# TY-PCB.net
KiCad netlist of a schematic drawn in EasyEDA Pro
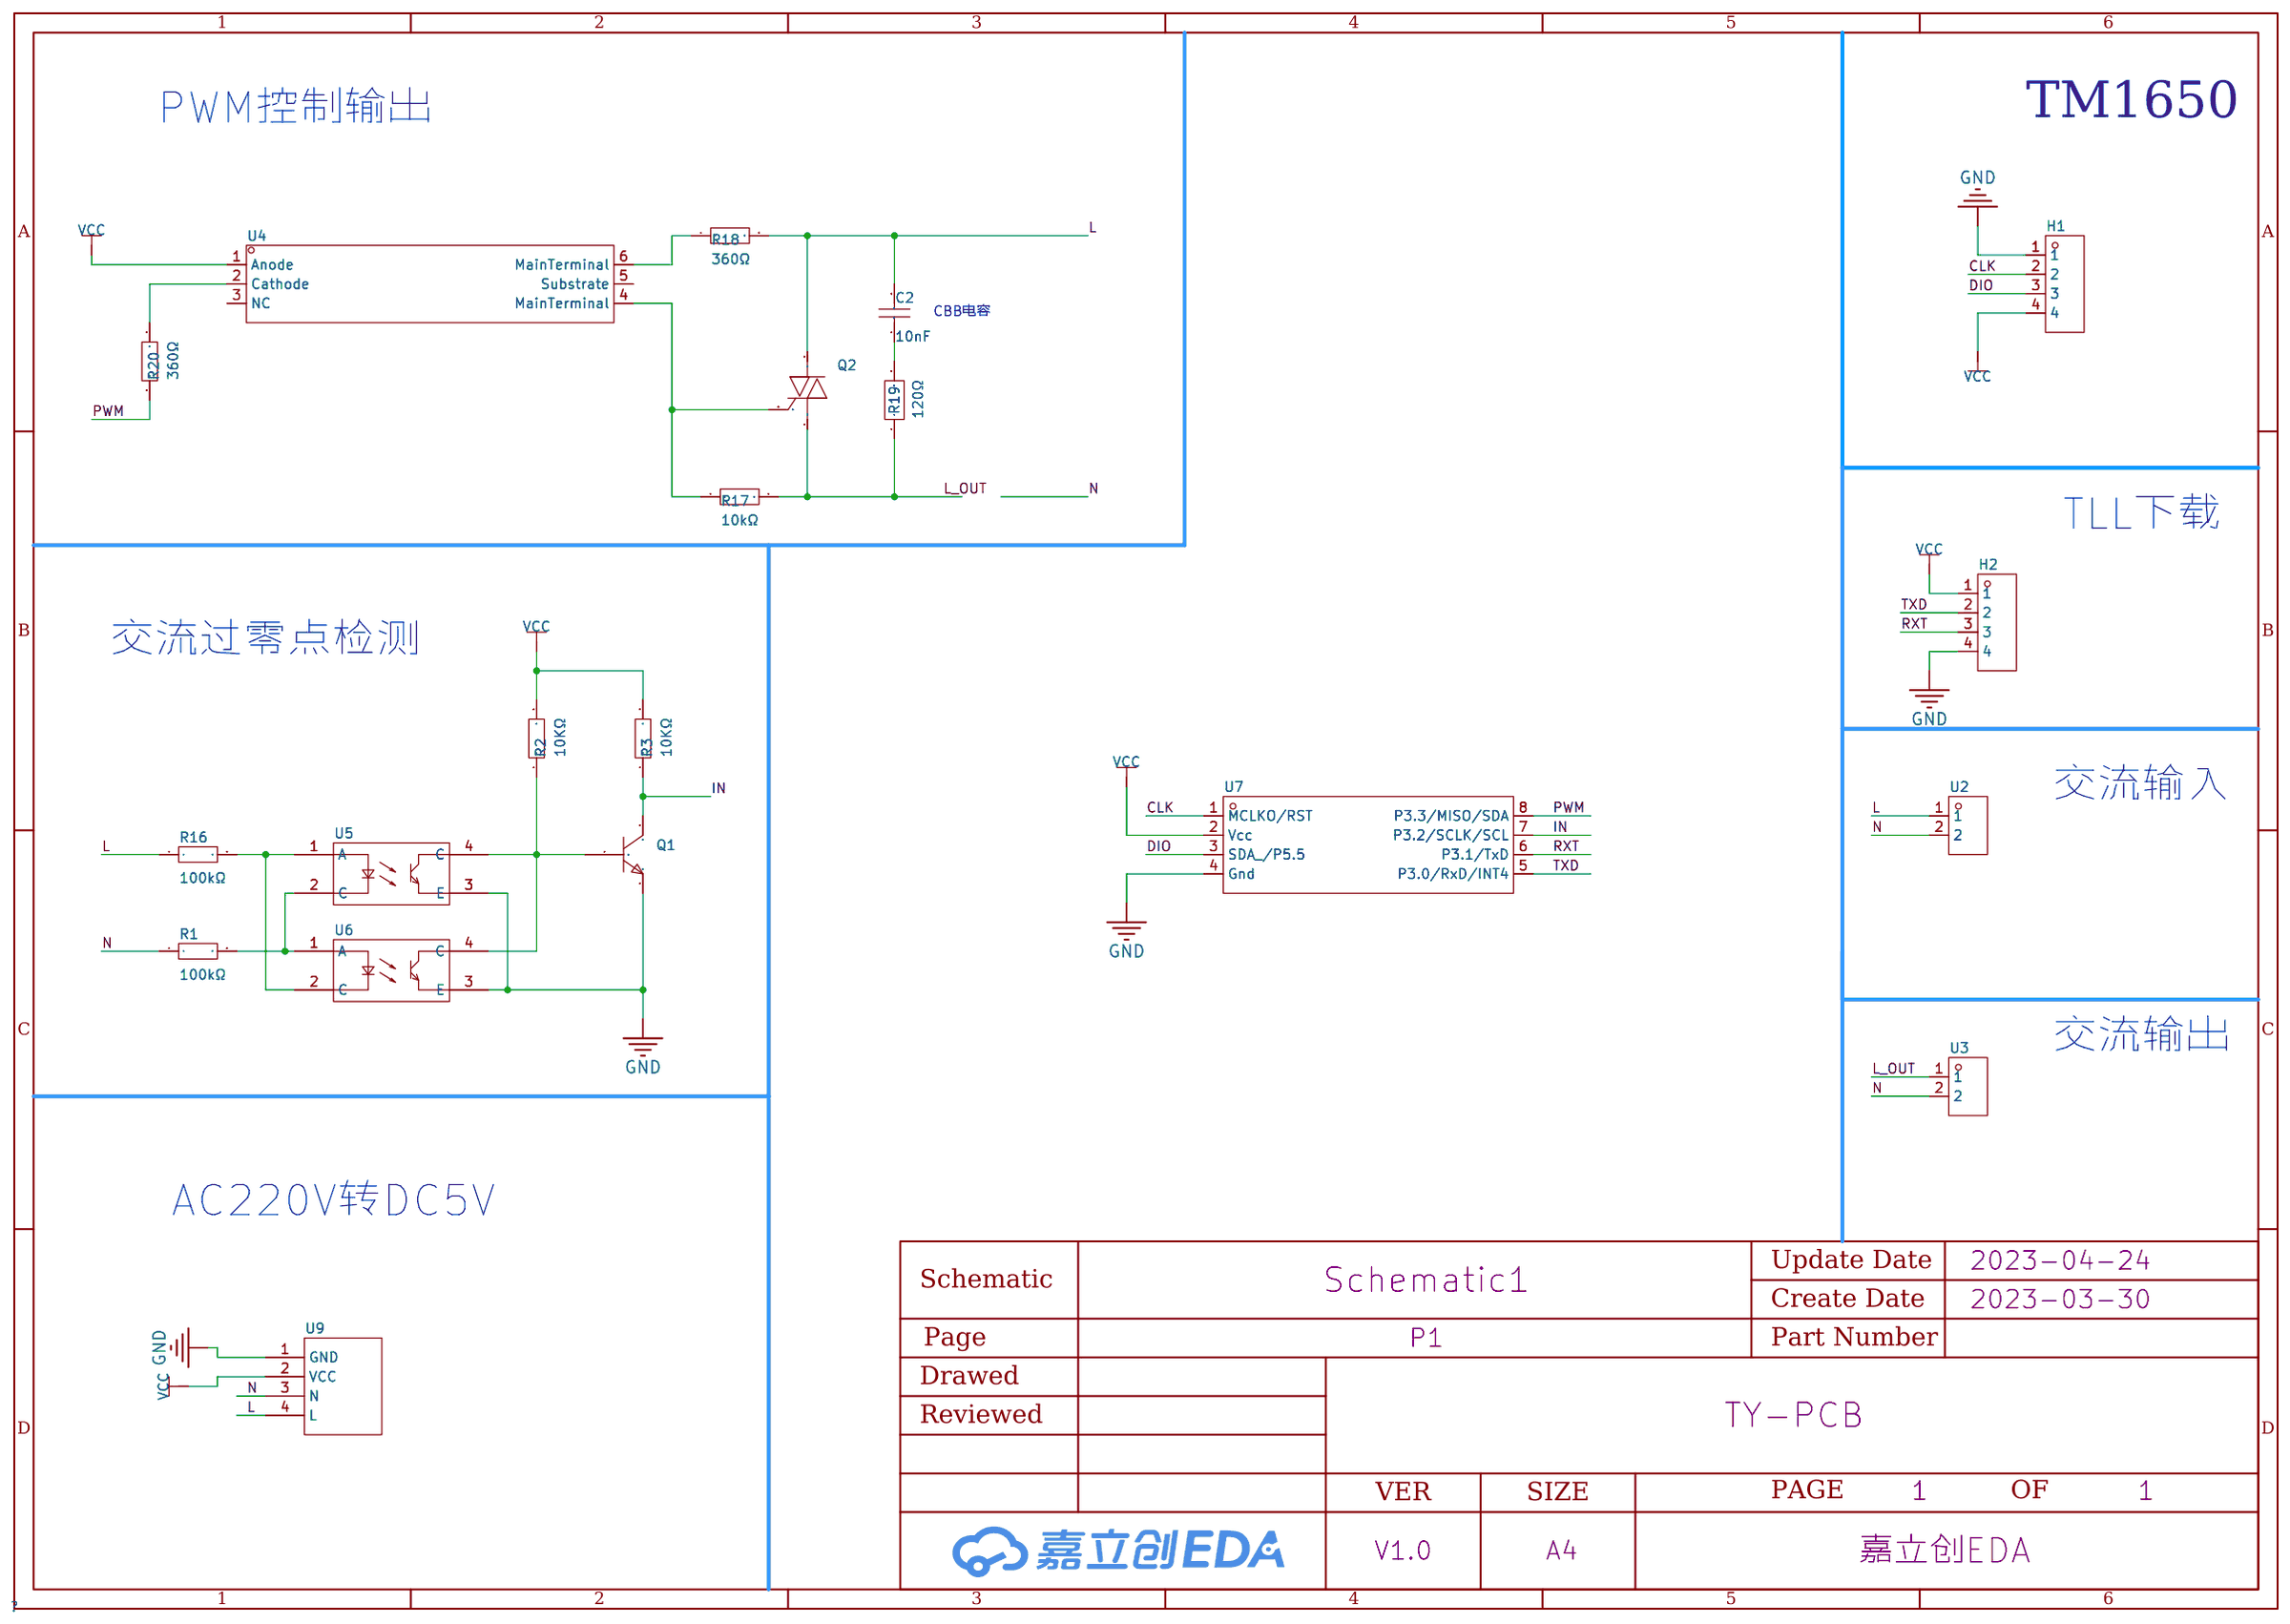
[diagram p0: schematic sheet]

(export (version "E")
  (design (tool "Eeschema 10.0.6"))
  (components
    (comp (ref "C2")
      (value "10nF")
      (footprint "easyedapro:CAP-TH_L13.0-W6.0-P10.00-D1.2")
      (description "容值:10nF;精度:±5%;额定电压:-;")
      (fields
        (field (name "Manufacturer Part") "MPP103J2J1304075LC")
        (field (name "Manufacturer") "SRD(圣融达)")
      )
      (libsource (lib "easyedapro") (part "MPP103J6130407LC"))
    )
    (comp (ref "H1")
      (value "826629-4")
      (footprint "easyedapro:HDR-TH_4P-P2.54-V-M-1")
      (fields (field (name "Manufacturer") "TE Connectivity(美国泰科)"))
      (libsource (lib "easyedapro") (part "826629-4"))
    )
    (comp (ref "H2")
      (value "826629-4")
      (footprint "easyedapro:HDR-TH_4P-P2.54-V-M-1")
      (fields (field (name "Manufacturer") "TE Connectivity(美国泰科)"))
      (libsource (lib "easyedapro") (part "826629-4"))
    )
    (comp (ref "Q1")
      (value "S8050")
      (footprint "easyedapro:TO-92-3_L4.9-W3.7-P1.27-L")
      (fields (field (name "Manufacturer") "CJ(江苏长电/长晶)"))
      (libsource (lib "easyedapro") (part "S8050_C141642"))
    )
    (comp (ref "Q2")
      (value "BTA06-800B")
      (footprint "easyedapro:TO-220-3_L10.0-W4.5-P2.54-L")
      (fields (field (name "Manufacturer") "KY(韩景元)"))
      (libsource (lib "easyedapro") (part "BTA06-800B_C2831698"))
    )
    (comp (ref "R1")
      (value "100kΩ")
      (footprint "easyedapro:R1210")
      (description "电阻类型:厚膜电阻;阻值:100kΩ;精度:±5%;功率:750mW;温度系数:±200ppm/°C;最大工作电压:200V;工作温度范围:-55°C~+125°C;")
      (fields (field (name "Manufacturer Part") "CR1210J30104G") (field (name "Manufacturer") "LIZ(丽智电子)"))
      (libsource (lib "easyedapro") (part "CR1210J30104G"))
    )
    (comp (ref "R2")
      (value "10KΩ")
      (footprint "easyedapro:R0805")
      (description "电阻类型:厚膜电阻;阻值:10kΩ;精度:±1%;功率:125mW;温度系数:±100ppm/℃;最大工作电压:150V;工作温度范围:-55℃~+155℃;")
      (fields
        (field (name "Manufacturer Part") "0805W8F1002T5E")
        (field (name "Manufacturer") "UNI-ROYAL(厚声)")
      )
      (libsource (lib "easyedapro") (part "0805W8F1002T5E"))
    )
    (comp (ref "R3")
      (value "10KΩ")
      (footprint "easyedapro:R0805")
      (description "电阻类型:厚膜电阻;阻值:10kΩ;精度:±1%;功率:125mW;温度系数:±100ppm/℃;最大工作电压:150V;工作温度范围:-55℃~+155℃;")
      (fields
        (field (name "Manufacturer Part") "0805W8F1002T5E")
        (field (name "Manufacturer") "UNI-ROYAL(厚声)")
      )
      (libsource (lib "easyedapro") (part "0805W8F1002T5E"))
    )
    (comp (ref "R16")
      (value "100kΩ")
      (footprint "easyedapro:R1210")
      (description "电阻类型:厚膜电阻;阻值:100kΩ;精度:±5%;功率:750mW;温度系数:±200ppm/°C;最大工作电压:200V;工作温度范围:-55°C~+125°C;")
      (fields (field (name "Manufacturer Part") "CR1210J30104G") (field (name "Manufacturer") "LIZ(丽智电子)"))
      (libsource (lib "easyedapro") (part "CR1210J30104G"))
    )
    (comp (ref "R17")
      (value "10kΩ")
      (footprint "easyedapro:R1210")
      (description "阻值:10kΩ;精度:±5%;功率:750mW;温度系数:±200ppm/°C;最大工作电压:200V;工作温度范围:-55°C~+155°C;")
      (fields (field (name "Manufacturer Part") "RK73B2ETTD103J") (field (name "Manufacturer") "KOA"))
      (libsource (lib "easyedapro") (part "RK73B2ETTD103J"))
    )
    (comp (ref "R18")
      (value "360Ω")
      (footprint "easyedapro:R1210")
      (description "电阻类型:厚膜电阻;阻值:360Ω;精度:±5%;功率:750mW;温度系数:±200ppm/°C;最大工作电压:200V;工作温度范围:-55°C~+125°C;")
      (fields (field (name "Manufacturer Part") "CR1210J30361G") (field (name "Manufacturer") "LIZ(丽智电子)"))
      (libsource (lib "easyedapro") (part "CR1210J30361G"))
    )
    (comp (ref "R19")
      (value "120Ω")
      (footprint "easyedapro:R2512")
      (description "阻值:120Ω;精度:±5%;功率:2W;最大工作电压:200V;工作温度范围:-55℃~+155℃;")
      (fields (field (name "Manufacturer Part") "RC2512JK-7W120RL") (field (name "Manufacturer") "YAGEO(国巨)"))
      (libsource (lib "easyedapro") (part "RC2512JK-7W120RL"))
    )
    (comp (ref "R20")
      (value "360Ω")
      (footprint "easyedapro:R0805")
      (description "电阻类型:厚膜电阻;阻值:10kΩ;精度:±1%;功率:125mW;温度系数:±100ppm/℃;最大工作电压:150V;工作温度范围:-55℃~+155℃;")
      (fields
        (field (name "Manufacturer Part") "0805W8F1002T5E")
        (field (name "Manufacturer") "UNI-ROYAL(厚声)")
      )
      (libsource (lib "easyedapro") (part "0805W8F1002T5E"))
    )
    (comp (ref "U2")
      (value "DB302-5.0-2P-GN-S")
      (footprint "easyedapro:CONN-TH_DB302-5.0-2P")
      (fields (field (name "Manufacturer") "DIBO(地博电气)"))
      (libsource (lib "easyedapro") (part "DB302-5.0-2P-GN-S"))
    )
    (comp (ref "U3")
      (value "DB302-5.0-2P-GN-S")
      (footprint "easyedapro:CONN-TH_DB302-5.0-2P")
      (fields (field (name "Manufacturer") "DIBO(地博电气)"))
      (libsource (lib "easyedapro") (part "DB302-5.0-2P-GN-S"))
    )
    (comp (ref "U4")
      (value "MOC3052S-V")
      (footprint "easyedapro:SOP-6_L8.5-W6.4-P2.54-LS9.2-BL")
      (fields (field (name "Manufacturer") "LITEON(光宝)"))
      (libsource (lib "easyedapro") (part "MOC3052S-V"))
    )
    (comp (ref "U5")
      (value "TLP521-1XGBSMT&R")
      (footprint "easyedapro:SOP-4_L6.4-W4.6-P2.54-LS10.2-BL")
      (fields (field (name "Manufacturer") "ISOCOM(英国安数光)"))
      (libsource (lib "easyedapro") (part "TLP521-1XGBSMT&amp;R"))
    )
    (comp (ref "U6")
      (value "TLP521-1XGBSMT&R")
      (footprint "easyedapro:SOP-4_L6.4-W4.6-P2.54-LS10.2-BL")
      (fields (field (name "Manufacturer") "ISOCOM(英国安数光)"))
      (libsource (lib "easyedapro") (part "TLP521-1XGBSMT&amp;R"))
    )
    (comp (ref "U7")
      (value "STC8G1K08-36I-SOP8")
      (footprint "easyedapro:SOP-8_L5.0-W4.0-P1.27-LS6.0-BL")
      (fields (field (name "Manufacturer") "STC(宏晶)"))
      (libsource (lib "easyedapro") (part "STC8G1K08-36I-SOP8"))
    )
    (comp (ref "U9")
      (value "~")
      (footprint "easyedapro:220V-5V")
      (libsource (lib "easyedapro") (part "220V-5V"))
    )
  )
  (nets
    (net (code "1") (name "/CLK") (class "Default")
      (node (ref "H1") (pin "2") (pinfunction "2_2") (pintype "input"))
      (node (ref "U7") (pin "1") (pinfunction "MCLKO/RST_1") (pintype "input"))
    )
    (net (code "2") (name "/DIO") (class "Default")
      (node (ref "H1") (pin "3") (pinfunction "3_3") (pintype "input"))
      (node (ref "U7") (pin "3") (pinfunction "SDA_/P5.5_3") (pintype "input"))
    )
    (net (code "3") (name "/IN") (class "Default")
      (node (ref "Q1") (pin "3") (pinfunction "C_3") (pintype "input"))
      (node (ref "R3") (pin "1") (pinfunction "1_1") (pintype "input"))
      (node (ref "U7") (pin "7") (pinfunction "P3.2/SCLK/SCL_7") (pintype "input"))
    )
    (net (code "4") (name "/L") (class "Default")
      (node (ref "C2") (pin "2") (pinfunction "2_2") (pintype "input"))
      (node (ref "Q2") (pin "2") (pinfunction "M2_2") (pintype "input"))
      (node (ref "R16") (pin "1") (pinfunction "1_1") (pintype "input"))
      (node (ref "R18") (pin "2") (pinfunction "2_2") (pintype "input"))
      (node (ref "U2") (pin "1") (pinfunction "1_1") (pintype "input"))
      (node (ref "U9") (pin "4") (pinfunction "L_4") (pintype "input"))
    )
    (net (code "5") (name "/L_OUT") (class "Default")
      (node (ref "Q2") (pin "1") (pinfunction "M1_1") (pintype "input"))
      (node (ref "R17") (pin "2") (pinfunction "2_2") (pintype "input"))
      (node (ref "R19") (pin "1") (pinfunction "1_1") (pintype "input"))
      (node (ref "U3") (pin "1") (pinfunction "1_1") (pintype "input"))
    )
    (net (code "6") (name "/N") (class "Default")
      (node (ref "R1") (pin "1") (pinfunction "1_1") (pintype "input"))
      (node (ref "U2") (pin "2") (pinfunction "2_2") (pintype "input"))
      (node (ref "U3") (pin "2") (pinfunction "2_2") (pintype "input"))
      (node (ref "U9") (pin "3") (pinfunction "N_3") (pintype "input"))
    )
    (net (code "7") (name "/PWM") (class "Default")
      (node (ref "R20") (pin "1") (pinfunction "1_1") (pintype "input"))
      (node (ref "U7") (pin "8") (pinfunction "P3.3/MISO/SDA_8") (pintype "input"))
    )
    (net (code "8") (name "/RXT") (class "Default")
      (node (ref "H2") (pin "3") (pinfunction "3_3") (pintype "input"))
      (node (ref "U7") (pin "6") (pinfunction "P3.1/TxD_6") (pintype "input"))
    )
    (net (code "9") (name "/TXD") (class "Default")
      (node (ref "H2") (pin "2") (pinfunction "2_2") (pintype "input"))
      (node (ref "U7") (pin "5") (pinfunction "P3.0/RxD/INT4_5") (pintype "input"))
    )
    (net (code "10") (name "GND") (class "Default")
      (node (ref "H1") (pin "1") (pinfunction "1_1") (pintype "input"))
      (node (ref "H2") (pin "4") (pinfunction "4_4") (pintype "input"))
      (node (ref "Q1") (pin "1") (pinfunction "E_1") (pintype "input"))
      (node (ref "U5") (pin "3") (pinfunction "E_3") (pintype "input"))
      (node (ref "U6") (pin "3") (pinfunction "E_3") (pintype "input"))
      (node (ref "U7") (pin "4") (pinfunction "Gnd_4") (pintype "input"))
      (node (ref "U9") (pin "1") (pinfunction "GND_1") (pintype "input"))
    )
    (net (code "11") (name "Net-(C2-Pad1)") (class "Default")
      (node (ref "C2") (pin "1") (pinfunction "1_1") (pintype "input"))
      (node (ref "R19") (pin "2") (pinfunction "2_2") (pintype "input"))
    )
    (net (code "12") (name "Net-(Q1-B)") (class "Default")
      (node (ref "Q1") (pin "2") (pinfunction "B_2") (pintype "input"))
      (node (ref "R2") (pin "1") (pinfunction "1_1") (pintype "input"))
      (node (ref "U5") (pin "4") (pinfunction "C_4") (pintype "input"))
      (node (ref "U6") (pin "4") (pinfunction "C_4") (pintype "input"))
    )
    (net (code "13") (name "Net-(Q2-G)") (class "Default")
      (node (ref "Q2") (pin "3") (pinfunction "G_3") (pintype "input"))
      (node (ref "R17") (pin "1") (pinfunction "1_1") (pintype "input"))
      (node (ref "U4") (pin "4") (pinfunction "MainTerminal_4") (pintype "input"))
    )
    (net (code "14") (name "Net-(R18-Pad1)") (class "Default")
      (node (ref "R18") (pin "1") (pinfunction "1_1") (pintype "input"))
      (node (ref "U4") (pin "6") (pinfunction "MainTerminal_6") (pintype "input"))
    )
    (net (code "15") (name "Net-(U4-Cathode)") (class "Default")
      (node (ref "R20") (pin "2") (pinfunction "2_2") (pintype "input"))
      (node (ref "U4") (pin "2") (pinfunction "Cathode_2") (pintype "input"))
    )
    (net (code "16") (name "Net-(U5-A)") (class "Default")
      (node (ref "R16") (pin "2") (pinfunction "2_2") (pintype "input"))
      (node (ref "U5") (pin "1") (pinfunction "A_1") (pintype "input"))
      (node (ref "U6") (pin "2") (pinfunction "C_2") (pintype "input"))
    )
    (net (code "17") (name "Net-(U6-A)") (class "Default")
      (node (ref "R1") (pin "2") (pinfunction "2_2") (pintype "input"))
      (node (ref "U5") (pin "2") (pinfunction "C_2") (pintype "input"))
      (node (ref "U6") (pin "1") (pinfunction "A_1") (pintype "input"))
    )
    (net (code "18") (name "VCC") (class "Default")
      (node (ref "H1") (pin "4") (pinfunction "4_4") (pintype "input"))
      (node (ref "H2") (pin "1") (pinfunction "1_1") (pintype "input"))
      (node (ref "R2") (pin "2") (pinfunction "2_2") (pintype "input"))
      (node (ref "R3") (pin "2") (pinfunction "2_2") (pintype "input"))
      (node (ref "U4") (pin "1") (pinfunction "Anode_1") (pintype "input"))
      (node (ref "U7") (pin "2") (pinfunction "Vcc_2") (pintype "input"))
      (node (ref "U9") (pin "2") (pinfunction "VCC_2") (pintype "input"))
    )
    (net (code "19") (name "unconnected-(U4-NC-Pad3)") (class "Default")
      (node (ref "U4") (pin "3") (pinfunction "NC_3") (pintype "input"))
    )
    (net (code "20") (name "unconnected-(U4-Substrate-Pad5)") (class "Default")
      (node (ref "U4") (pin "5") (pinfunction "Substrate_5") (pintype "input"))
    )
  )
)
